# Crystal_Cmoy_Sch_EaglePCB_1.net
KiCad netlist of a schematic drawn in EAGLE
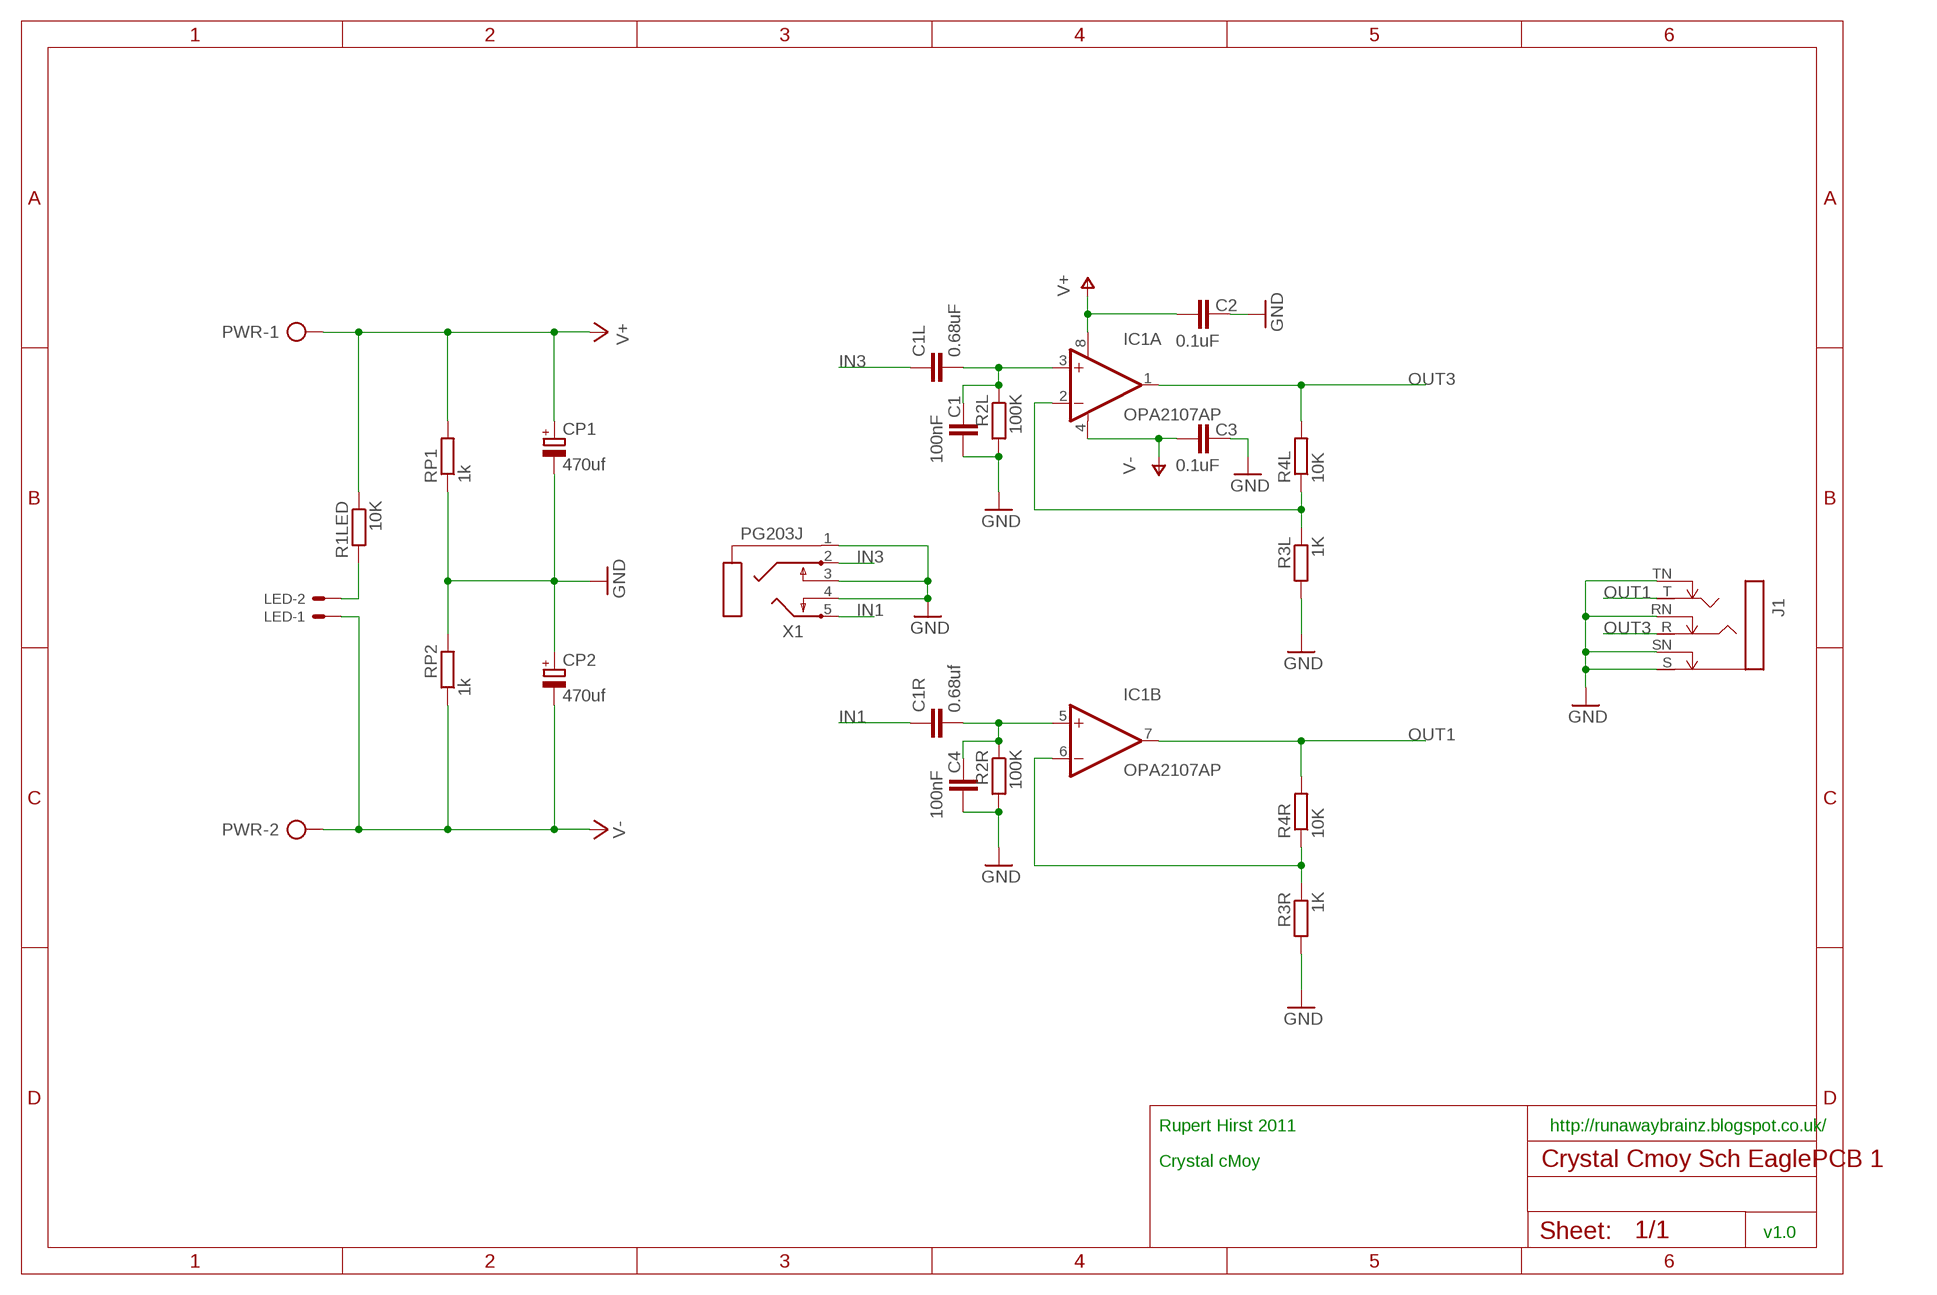
[diagram p0: schematic, sheet 1]

(export (version "E")
  (design (tool "Eeschema 10.0.6"))
  (components
    (comp (ref "C1")
      (value "100nF")
      (footprint "eagle-import:C025-025X050")
      (libsource (lib "eagle-import") (part "C-EU025-025X050"))
    )
    (comp (ref "C1L")
      (value "0.68uF")
      (footprint "eagle-import:C5B4.5")
      (libsource (lib "eagle-import") (part "capacitor-wima_116_C5/4.5"))
    )
    (comp (ref "C1R")
      (value "0.68uf")
      (footprint "eagle-import:C5B4.5")
      (libsource (lib "eagle-import") (part "capacitor-wima_116_C5/4.5"))
    )
    (comp (ref "C2")
      (value "0.1uF")
      (footprint "eagle-import:C5B2.5")
      (libsource (lib "eagle-import") (part "C5/2.5"))
    )
    (comp (ref "C3")
      (value "0.1uF")
      (footprint "eagle-import:C5B2.5")
      (libsource (lib "eagle-import") (part "C5/2.5"))
    )
    (comp (ref "C4")
      (value "100nF")
      (footprint "eagle-import:C025-025X050")
      (libsource (lib "eagle-import") (part "C-EU025-025X050"))
    )
    (comp (ref "CP1")
      (value "470uf")
      (footprint "eagle-import:E5-13")
      (libsource (lib "eagle-import") (part "CPOL-EUE5-13"))
    )
    (comp (ref "CP2")
      (value "470uf")
      (footprint "eagle-import:E5-13")
      (libsource (lib "eagle-import") (part "CPOL-EUE5-13"))
    )
    (comp (ref "IC1")
      (value "OPA2107AP")
      (footprint "eagle-import:DIL08")
      (libsource (lib "eagle-import") (part "OPA2132P"))
    )
    (comp (ref "J1")
      (value "STEREOSW")
      (footprint "eagle-import:NMJ6HCD2")
      (libsource (lib "eagle-import") (part "STEREOSW"))
    )
    (comp (ref "LED")
      (value "22-23-2021")
      (footprint "eagle-import:22-23-2021")
      (fields (field (name "MF") "MOLEX"))
      (libsource (lib "eagle-import") (part "22-23-2021"))
    )
    (comp (ref "PWR")
      (value "AK500/2")
      (footprint "eagle-import:AK500_2")
      (libsource (lib "eagle-import") (part "AK500/2"))
    )
    (comp (ref "R1LED")
      (value "10K")
      (footprint "eagle-import:0411_15")
      (libsource (lib "eagle-import") (part "R-EU_0411/15"))
    )
    (comp (ref "R2L")
      (value "100K")
      (footprint "eagle-import:0411_15")
      (libsource (lib "eagle-import") (part "R-EU_0411/15"))
    )
    (comp (ref "R2R")
      (value "100K")
      (footprint "eagle-import:0411_15")
      (libsource (lib "eagle-import") (part "R-EU_0411/15"))
    )
    (comp (ref "R3L")
      (value "1K")
      (footprint "eagle-import:0411_15")
      (libsource (lib "eagle-import") (part "R-EU_0411/15"))
    )
    (comp (ref "R3R")
      (value "1K")
      (footprint "eagle-import:0411_15")
      (libsource (lib "eagle-import") (part "R-EU_0411/15"))
    )
    (comp (ref "R4L")
      (value "10K")
      (footprint "eagle-import:0411_15")
      (libsource (lib "eagle-import") (part "R-EU_0411/15"))
    )
    (comp (ref "R4R")
      (value "10K")
      (footprint "eagle-import:0411_15")
      (libsource (lib "eagle-import") (part "R-EU_0411/15"))
    )
    (comp (ref "RP1")
      (value "1k")
      (footprint "eagle-import:0411_15")
      (libsource (lib "eagle-import") (part "R-EU_0411/15"))
    )
    (comp (ref "RP2")
      (value "1k")
      (footprint "eagle-import:0411_15")
      (libsource (lib "eagle-import") (part "R-EU_0411/15"))
    )
    (comp (ref "X1")
      (value "PG203J")
      (footprint "eagle-import:PG203J")
      (libsource (lib "eagle-import") (part "PG203J"))
    )
  )
  (nets
    (net (code "1") (name "/IN1") (class "Default")
      (node (ref "C1R") (pin "1") (pinfunction "1_1") (pintype "passive"))
      (node (ref "X1") (pin "5") (pinfunction "5_5") (pintype "passive"))
    )
    (net (code "2") (name "/IN3") (class "Default")
      (node (ref "C1L") (pin "1") (pinfunction "1_1") (pintype "passive"))
      (node (ref "X1") (pin "2") (pinfunction "2_2") (pintype "passive"))
    )
    (net (code "3") (name "/OUT1") (class "Default")
      (node (ref "IC1") (pin "7") (pinfunction "OUT_7") (pintype "output"))
      (node (ref "J1") (pin "T") (pinfunction "T_T") (pintype "passive"))
      (node (ref "R4R") (pin "2") (pinfunction "2_2") (pintype "passive"))
    )
    (net (code "4") (name "/OUT3") (class "Default")
      (node (ref "IC1") (pin "1") (pinfunction "OUT_1") (pintype "output"))
      (node (ref "J1") (pin "R") (pinfunction "R_R") (pintype "passive"))
      (node (ref "R4L") (pin "2") (pinfunction "2_2") (pintype "passive"))
    )
    (net (code "5") (name "GND") (class "Default")
      (node (ref "C1") (pin "2") (pinfunction "2_2") (pintype "passive"))
      (node (ref "C2") (pin "1") (pinfunction "1_1") (pintype "passive"))
      (node (ref "C3") (pin "1") (pinfunction "1_1") (pintype "passive"))
      (node (ref "C4") (pin "2") (pinfunction "2_2") (pintype "passive"))
      (node (ref "CP1") (pin "-") (pinfunction "-_-") (pintype "passive"))
      (node (ref "CP2") (pin "+") (pinfunction "+_+") (pintype "passive"))
      (node (ref "J1") (pin "RN") (pinfunction "RN_RN") (pintype "passive"))
      (node (ref "J1") (pin "S") (pinfunction "S_S") (pintype "passive"))
      (node (ref "J1") (pin "SN") (pinfunction "SN_SN") (pintype "passive"))
      (node (ref "J1") (pin "TN") (pinfunction "TN_TN") (pintype "passive"))
      (node (ref "R2L") (pin "2") (pinfunction "2_2") (pintype "passive"))
      (node (ref "R2R") (pin "2") (pinfunction "2_2") (pintype "passive"))
      (node (ref "R3L") (pin "2") (pinfunction "2_2") (pintype "passive"))
      (node (ref "R3R") (pin "2") (pinfunction "2_2") (pintype "passive"))
      (node (ref "RP1") (pin "1") (pinfunction "1_1") (pintype "passive"))
      (node (ref "RP2") (pin "2") (pinfunction "2_2") (pintype "passive"))
      (node (ref "X1") (pin "1") (pinfunction "1_1") (pintype "passive"))
      (node (ref "X1") (pin "3") (pinfunction "3_3") (pintype "passive"))
      (node (ref "X1") (pin "4") (pinfunction "4_4") (pintype "passive"))
    )
    (net (code "6") (name "Net-(IC1A-+IN)") (class "Default")
      (node (ref "C1") (pin "1") (pinfunction "1_1") (pintype "passive"))
      (node (ref "C1L") (pin "2") (pinfunction "2_2") (pintype "passive"))
      (node (ref "IC1") (pin "3") (pinfunction "+IN_3") (pintype "input"))
      (node (ref "R2L") (pin "1") (pinfunction "1_1") (pintype "passive"))
    )
    (net (code "7") (name "Net-(IC1A--IN)") (class "Default")
      (node (ref "IC1") (pin "2") (pinfunction "-IN_2") (pintype "input"))
      (node (ref "R3L") (pin "1") (pinfunction "1_1") (pintype "passive"))
      (node (ref "R4L") (pin "1") (pinfunction "1_1") (pintype "passive"))
    )
    (net (code "8") (name "Net-(IC1B-+IN)") (class "Default")
      (node (ref "C1R") (pin "2") (pinfunction "2_2") (pintype "passive"))
      (node (ref "C4") (pin "1") (pinfunction "1_1") (pintype "passive"))
      (node (ref "IC1") (pin "5") (pinfunction "+IN_5") (pintype "input"))
      (node (ref "R2R") (pin "1") (pinfunction "1_1") (pintype "passive"))
    )
    (net (code "9") (name "Net-(IC1B--IN)") (class "Default")
      (node (ref "IC1") (pin "6") (pinfunction "-IN_6") (pintype "input"))
      (node (ref "R3R") (pin "1") (pinfunction "1_1") (pintype "passive"))
      (node (ref "R4R") (pin "1") (pinfunction "1_1") (pintype "passive"))
    )
    (net (code "10") (name "Net-(LEDB-S)") (class "Default")
      (node (ref "LED") (pin "2") (pinfunction "S_2") (pintype "passive"))
      (node (ref "R1LED") (pin "2") (pinfunction "2_2") (pintype "passive"))
    )
    (net (code "11") (name "V+") (class "Default")
      (node (ref "C2") (pin "2") (pinfunction "2_2") (pintype "passive"))
      (node (ref "CP1") (pin "+") (pinfunction "+_+") (pintype "passive"))
      (node (ref "IC1") (pin "8") (pinfunction "V+_8") (pintype "power_in"))
      (node (ref "PWR") (pin "1") (pinfunction "KL_1") (pintype "passive"))
      (node (ref "R1LED") (pin "1") (pinfunction "1_1") (pintype "passive"))
      (node (ref "RP1") (pin "2") (pinfunction "2_2") (pintype "passive"))
    )
    (net (code "12") (name "V-") (class "Default")
      (node (ref "C3") (pin "2") (pinfunction "2_2") (pintype "passive"))
      (node (ref "CP2") (pin "-") (pinfunction "-_-") (pintype "passive"))
      (node (ref "IC1") (pin "4") (pinfunction "V-_4") (pintype "power_in"))
      (node (ref "LED") (pin "1") (pinfunction "S_1") (pintype "passive"))
      (node (ref "PWR") (pin "2") (pinfunction "KL_2") (pintype "passive"))
      (node (ref "RP2") (pin "1") (pinfunction "1_1") (pintype "passive"))
    )
  )
)
